# S7CAS-PLEIADES-CARTE-MERE_P06_FPGA1.net
KiCad netlist of a schematic drawn in Altium Designer
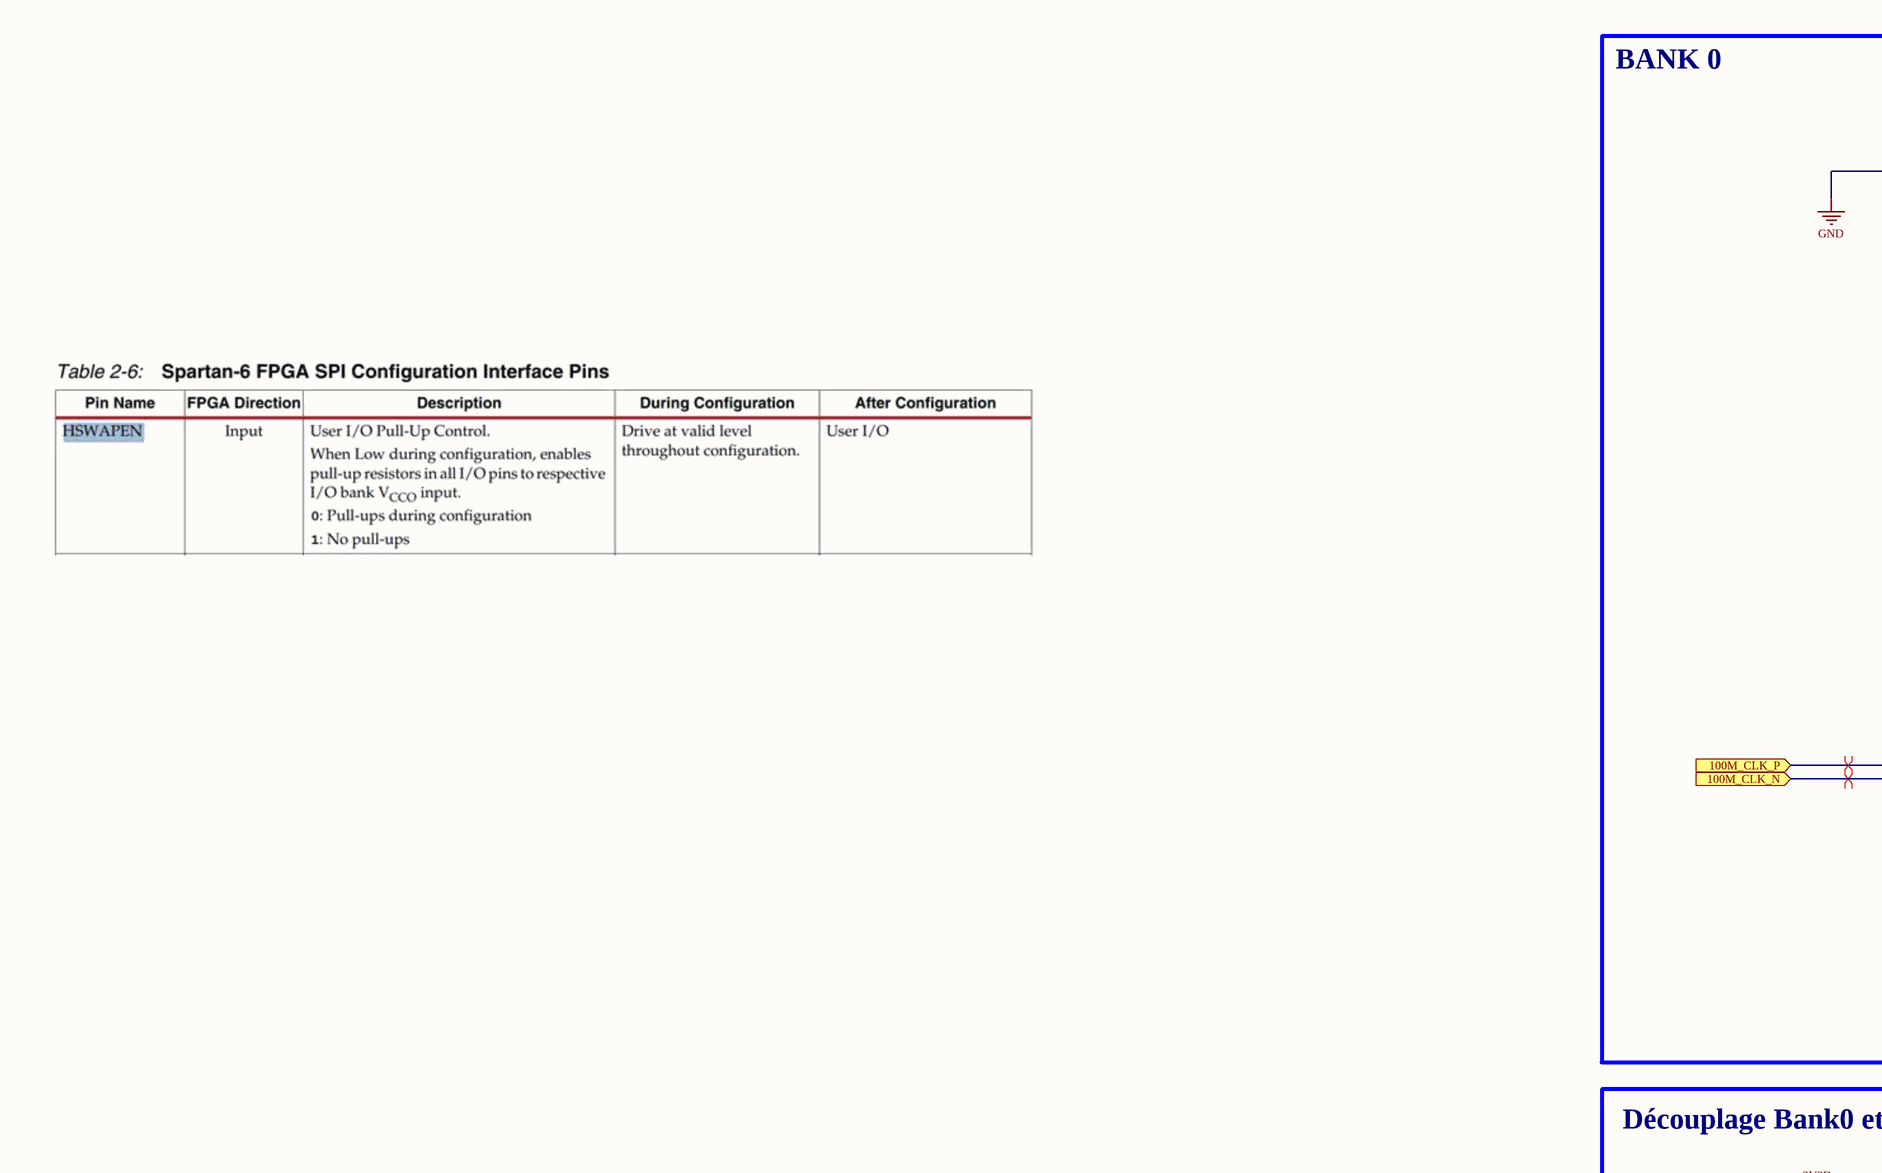
[diagram p0: S7CAS-PLEIADES-CARTE-MERE_P06_FPGA1.SCHDOC, top left]
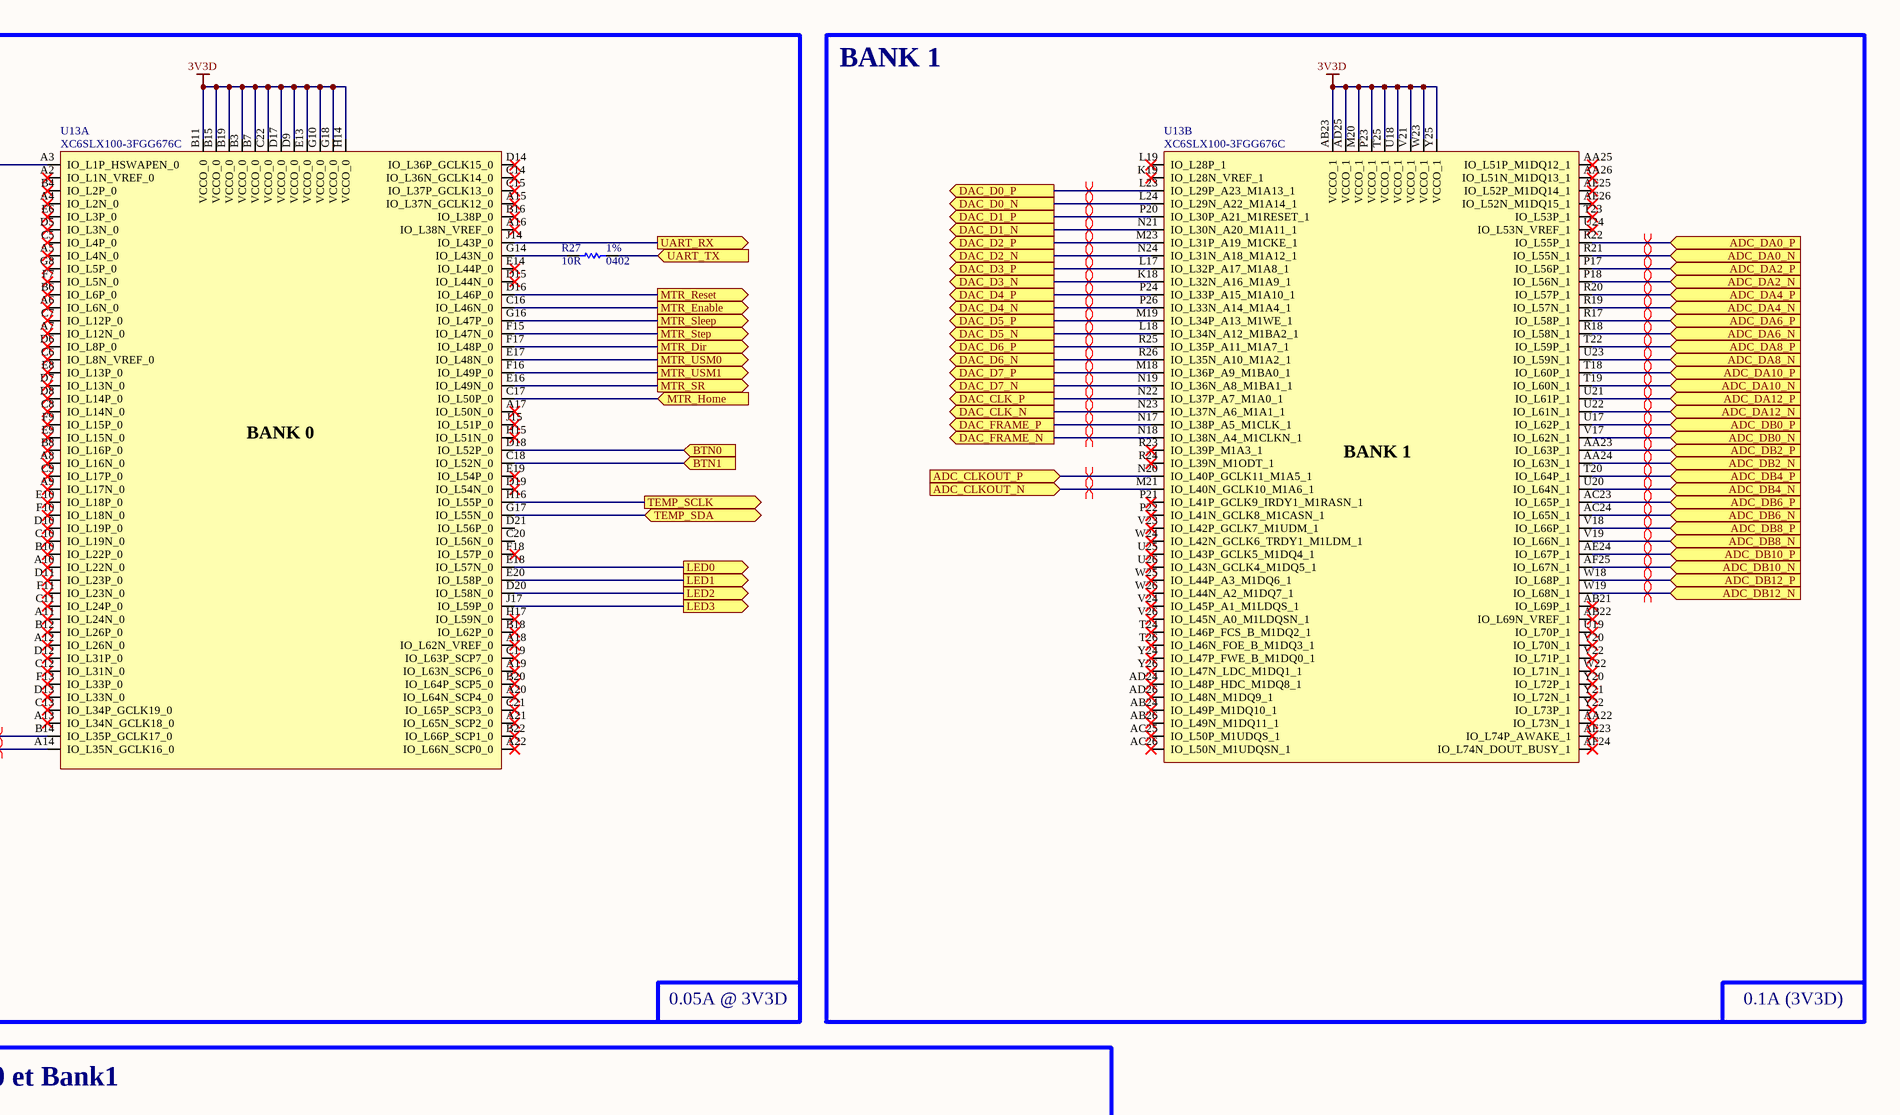
[diagram p1: S7CAS-PLEIADES-CARTE-MERE_P06_FPGA1.SCHDOC, top right]
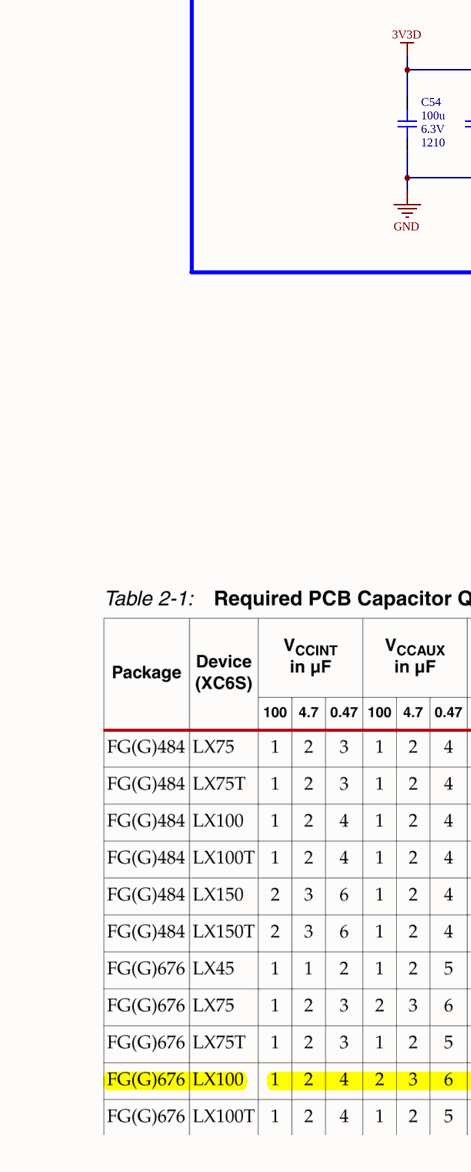
[diagram p2: S7CAS-PLEIADES-CARTE-MERE_P06_FPGA1.SCHDOC, bottom left]
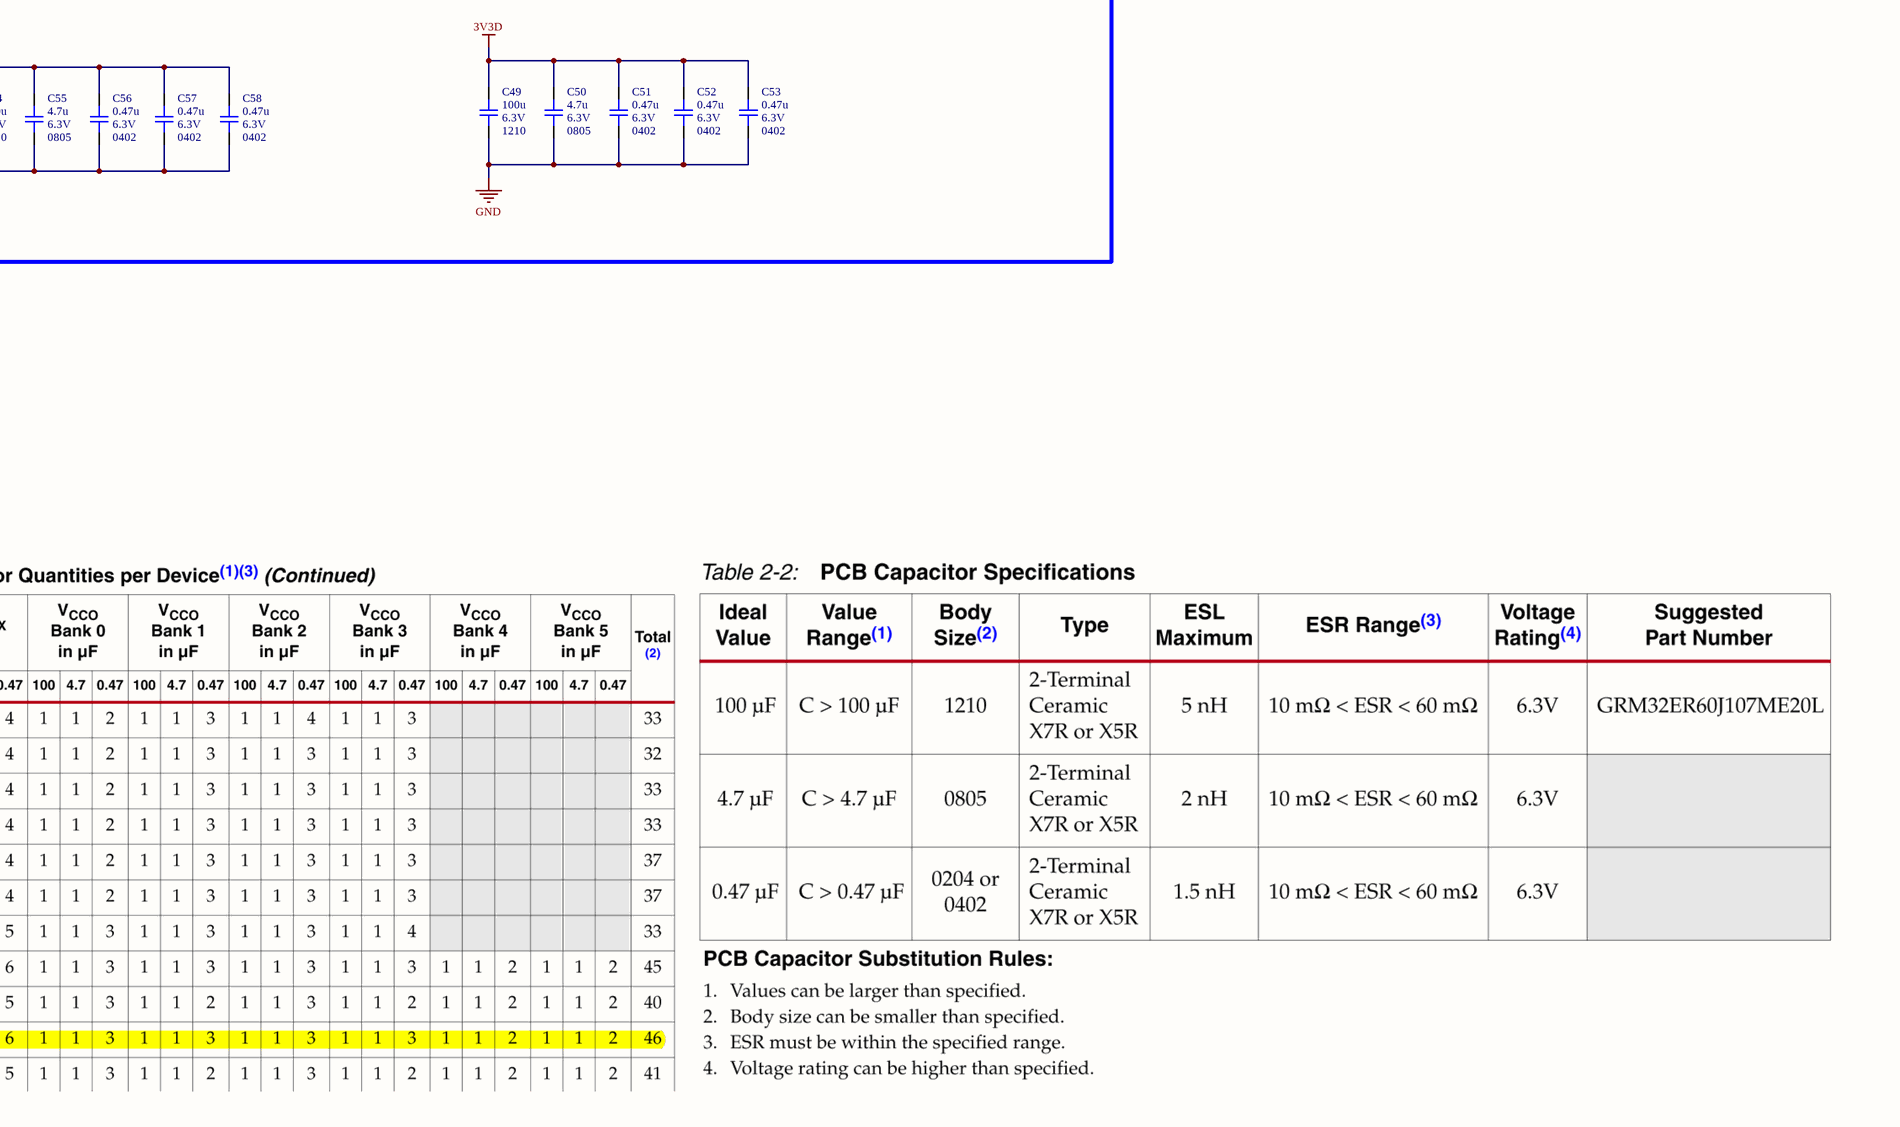
[diagram p3: S7CAS-PLEIADES-CARTE-MERE_P06_FPGA1.SCHDOC, bottom right]

(export (version "E")
  (design (tool "Eeschema 10.0.6"))
  (components
    (comp (ref "C49")
      (value "100u")
      (footprint "CAP_1210")
      (description "CAP - 1210")
      (fields
        (field (name "VOLTAGE") "6.3V")
        (field (name "PACKAGE") "1210")
        (field (name "CREATEDBY") "Jonathan Bouchard")
      )
      (libsource (lib "s7cas_lib2023") (part "CAP - 1210"))
    )
    (comp (ref "C50")
      (value "4.7u")
      (footprint "CAP_0805")
      (description "CAP - 0805")
      (fields
        (field (name "VOLTAGE") "6.3V")
        (field (name "PACKAGE") "0805")
        (field (name "CREATEDBY") "Jonathan Bouchard")
      )
      (libsource (lib "s7cas_lib2023") (part "CAP - 0805"))
    )
    (comp (ref "C51")
      (value "0.47u")
      (footprint "CAP_0402")
      (description "CAP - 0402")
      (fields
        (field (name "VOLTAGE") "6.3V")
        (field (name "PACKAGE") "0402")
        (field (name "CREATEDBY") "Jonathan Bouchard")
      )
      (libsource (lib "s7cas_lib2023") (part "CAP - 0402"))
    )
    (comp (ref "C52")
      (value "0.47u")
      (footprint "CAP_0402")
      (description "CAP - 0402")
      (fields
        (field (name "VOLTAGE") "6.3V")
        (field (name "PACKAGE") "0402")
        (field (name "CREATEDBY") "Jonathan Bouchard")
      )
      (libsource (lib "s7cas_lib2023") (part "CAP - 0402"))
    )
    (comp (ref "C53")
      (value "0.47u")
      (footprint "CAP_0402")
      (description "CAP - 0402")
      (fields
        (field (name "VOLTAGE") "6.3V")
        (field (name "PACKAGE") "0402")
        (field (name "CREATEDBY") "Jonathan Bouchard")
      )
      (libsource (lib "s7cas_lib2023") (part "CAP - 0402"))
    )
    (comp (ref "C54")
      (value "100u")
      (footprint "CAP_1210")
      (description "CAP - 1210")
      (fields
        (field (name "VOLTAGE") "6.3V")
        (field (name "PACKAGE") "1210")
        (field (name "CREATEDBY") "Jonathan Bouchard")
      )
      (libsource (lib "s7cas_lib2023") (part "CAP - 1210"))
    )
    (comp (ref "C55")
      (value "4.7u")
      (footprint "CAP_0805")
      (description "CAP - 0805")
      (fields
        (field (name "VOLTAGE") "6.3V")
        (field (name "PACKAGE") "0805")
        (field (name "CREATEDBY") "Jonathan Bouchard")
      )
      (libsource (lib "s7cas_lib2023") (part "CAP - 0805"))
    )
    (comp (ref "C56")
      (value "0.47u")
      (footprint "CAP_0402")
      (description "CAP - 0402")
      (fields
        (field (name "VOLTAGE") "6.3V")
        (field (name "PACKAGE") "0402")
        (field (name "CREATEDBY") "Jonathan Bouchard")
      )
      (libsource (lib "s7cas_lib2023") (part "CAP - 0402"))
    )
    (comp (ref "C57")
      (value "0.47u")
      (footprint "CAP_0402")
      (description "CAP - 0402")
      (fields
        (field (name "VOLTAGE") "6.3V")
        (field (name "PACKAGE") "0402")
        (field (name "CREATEDBY") "Jonathan Bouchard")
      )
      (libsource (lib "s7cas_lib2023") (part "CAP - 0402"))
    )
    (comp (ref "C58")
      (value "0.47u")
      (footprint "CAP_0402")
      (description "CAP - 0402")
      (fields
        (field (name "VOLTAGE") "6.3V")
        (field (name "PACKAGE") "0402")
        (field (name "CREATEDBY") "Jonathan Bouchard")
      )
      (libsource (lib "s7cas_lib2023") (part "CAP - 0402"))
    )
    (comp (ref "R27")
      (value "10R")
      (footprint "RES_0402")
      (description "RES - 10R 1% 1/16W - 0402")
      (fields
        (field (name "TOLERANCE") "1%")
        (field (name "PACKAGE") "0402")
        (field (name "Comment") "RMCF0402FT10R0")
        (field (name "CREATEDBY/DATE") "Joel Lemay 2018-07-04")
        (field (name "VERIFIEDBY") "Caroline Paulin - 6 sept 2018")
      )
      (libsource (lib "GRAMS_MASTER_LIB") (part "RES_RMCF0402FT10R0"))
    )
    (comp (ref "U13")
      (value "XC6SLX100-3FGG676C")
      (footprint "FPGA_XILINX_FGG676")
      (description "FPGA - XILINX SPARTAN 6 480 I/O - BGA-676")
      (fields
        (field (name "VOLTAGE") "1.14 V ~ 1.26 V")
        (field (name "MFG") "Xilinx")
        (field (name "CREATEDBY") "Jonathan Bouchard")
      )
      (libsource (lib "s7cas_lib2023") (part "FPGA_XC6SLX100-3FGG676C"))
    )
  )
  (nets
    (net (code "1") (name "/100M_CLK_N") (class "Default")
      (node (ref "U13") (pin "A14") (pinfunction "IO_L35N_GCLK16_0_A14") (pintype "passive"))
    )
    (net (code "2") (name "/100M_CLK_P") (class "Default")
      (node (ref "U13") (pin "B14") (pinfunction "IO_L35P_GCLK17_0_B14") (pintype "passive"))
    )
    (net (code "3") (name "/ADC_CLKOUT_N") (class "Default")
      (node (ref "U13") (pin "M21") (pinfunction "IO_L40N_GCLK10_M1A6_1_M21") (pintype "passive"))
    )
    (net (code "4") (name "/ADC_CLKOUT_P") (class "Default")
      (node (ref "U13") (pin "N20") (pinfunction "IO_L40P_GCLK11_M1A5_1_N20") (pintype "passive"))
    )
    (net (code "5") (name "/ADC_DA0_N") (class "Default")
      (node (ref "U13") (pin "R21") (pinfunction "IO_L55N_1_R21") (pintype "passive"))
    )
    (net (code "6") (name "/ADC_DA0_P") (class "Default")
      (node (ref "U13") (pin "R22") (pinfunction "IO_L55P_1_R22") (pintype "passive"))
    )
    (net (code "7") (name "/ADC_DA2_N") (class "Default")
      (node (ref "U13") (pin "P18") (pinfunction "IO_L56N_1_P18") (pintype "passive"))
    )
    (net (code "8") (name "/ADC_DA2_P") (class "Default")
      (node (ref "U13") (pin "P17") (pinfunction "IO_L56P_1_P17") (pintype "passive"))
    )
    (net (code "9") (name "/ADC_DA4_N") (class "Default")
      (node (ref "U13") (pin "R19") (pinfunction "IO_L57N_1_R19") (pintype "passive"))
    )
    (net (code "10") (name "/ADC_DA4_P") (class "Default")
      (node (ref "U13") (pin "R20") (pinfunction "IO_L57P_1_R20") (pintype "passive"))
    )
    (net (code "11") (name "/ADC_DA6_N") (class "Default")
      (node (ref "U13") (pin "R18") (pinfunction "IO_L58N_1_R18") (pintype "passive"))
    )
    (net (code "12") (name "/ADC_DA6_P") (class "Default")
      (node (ref "U13") (pin "R17") (pinfunction "IO_L58P_1_R17") (pintype "passive"))
    )
    (net (code "13") (name "/ADC_DA8_N") (class "Default")
      (node (ref "U13") (pin "U23") (pinfunction "IO_L59N_1_U23") (pintype "passive"))
    )
    (net (code "14") (name "/ADC_DA8_P") (class "Default")
      (node (ref "U13") (pin "T22") (pinfunction "IO_L59P_1_T22") (pintype "passive"))
    )
    (net (code "15") (name "/ADC_DA10_N") (class "Default")
      (node (ref "U13") (pin "T19") (pinfunction "IO_L60N_1_T19") (pintype "passive"))
    )
    (net (code "16") (name "/ADC_DA10_P") (class "Default")
      (node (ref "U13") (pin "T18") (pinfunction "IO_L60P_1_T18") (pintype "passive"))
    )
    (net (code "17") (name "/ADC_DA12_N") (class "Default")
      (node (ref "U13") (pin "U22") (pinfunction "IO_L61N_1_U22") (pintype "passive"))
    )
    (net (code "18") (name "/ADC_DA12_P") (class "Default")
      (node (ref "U13") (pin "U21") (pinfunction "IO_L61P_1_U21") (pintype "passive"))
    )
    (net (code "19") (name "/ADC_DB0_N") (class "Default")
      (node (ref "U13") (pin "V17") (pinfunction "IO_L62N_1_V17") (pintype "passive"))
    )
    (net (code "20") (name "/ADC_DB0_P") (class "Default")
      (node (ref "U13") (pin "U17") (pinfunction "IO_L62P_1_U17") (pintype "passive"))
    )
    (net (code "21") (name "/ADC_DB2_N") (class "Default")
      (node (ref "U13") (pin "AA24") (pinfunction "IO_L63N_1_AA24") (pintype "passive"))
    )
    (net (code "22") (name "/ADC_DB2_P") (class "Default")
      (node (ref "U13") (pin "AA23") (pinfunction "IO_L63P_1_AA23") (pintype "passive"))
    )
    (net (code "23") (name "/ADC_DB4_N") (class "Default")
      (node (ref "U13") (pin "U20") (pinfunction "IO_L64N_1_U20") (pintype "passive"))
    )
    (net (code "24") (name "/ADC_DB4_P") (class "Default")
      (node (ref "U13") (pin "T20") (pinfunction "IO_L64P_1_T20") (pintype "passive"))
    )
    (net (code "25") (name "/ADC_DB6_N") (class "Default")
      (node (ref "U13") (pin "AC24") (pinfunction "IO_L65N_1_AC24") (pintype "passive"))
    )
    (net (code "26") (name "/ADC_DB6_P") (class "Default")
      (node (ref "U13") (pin "AC23") (pinfunction "IO_L65P_1_AC23") (pintype "passive"))
    )
    (net (code "27") (name "/ADC_DB8_N") (class "Default")
      (node (ref "U13") (pin "V19") (pinfunction "IO_L66N_1_V19") (pintype "passive"))
    )
    (net (code "28") (name "/ADC_DB8_P") (class "Default")
      (node (ref "U13") (pin "V18") (pinfunction "IO_L66P_1_V18") (pintype "passive"))
    )
    (net (code "29") (name "/ADC_DB10_N") (class "Default")
      (node (ref "U13") (pin "AF25") (pinfunction "IO_L67N_1_AF25") (pintype "passive"))
    )
    (net (code "30") (name "/ADC_DB10_P") (class "Default")
      (node (ref "U13") (pin "AE24") (pinfunction "IO_L67P_1_AE24") (pintype "passive"))
    )
    (net (code "31") (name "/ADC_DB12_N") (class "Default")
      (node (ref "U13") (pin "W19") (pinfunction "IO_L68N_1_W19") (pintype "passive"))
    )
    (net (code "32") (name "/ADC_DB12_P") (class "Default")
      (node (ref "U13") (pin "W18") (pinfunction "IO_L68P_1_W18") (pintype "passive"))
    )
    (net (code "33") (name "/BTN0") (class "Default")
      (node (ref "U13") (pin "D18") (pinfunction "IO_L52P_0_D18") (pintype "passive"))
    )
    (net (code "34") (name "/BTN1") (class "Default")
      (node (ref "U13") (pin "C18") (pinfunction "IO_L52N_0_C18") (pintype "passive"))
    )
    (net (code "35") (name "/DAC_CLK_N") (class "Default")
      (node (ref "U13") (pin "N23") (pinfunction "IO_L37N_A6_M1A1_1_N23") (pintype "passive"))
    )
    (net (code "36") (name "/DAC_CLK_P") (class "Default")
      (node (ref "U13") (pin "N22") (pinfunction "IO_L37P_A7_M1A0_1_N22") (pintype "passive"))
    )
    (net (code "37") (name "/DAC_D0_N") (class "Default")
      (node (ref "U13") (pin "L24") (pinfunction "IO_L29N_A22_M1A14_1_L24") (pintype "passive"))
    )
    (net (code "38") (name "/DAC_D0_P") (class "Default")
      (node (ref "U13") (pin "L23") (pinfunction "IO_L29P_A23_M1A13_1_L23") (pintype "passive"))
    )
    (net (code "39") (name "/DAC_D1_N") (class "Default")
      (node (ref "U13") (pin "N21") (pinfunction "IO_L30N_A20_M1A11_1_N21") (pintype "passive"))
    )
    (net (code "40") (name "/DAC_D1_P") (class "Default")
      (node (ref "U13") (pin "P20") (pinfunction "IO_L30P_A21_M1RESET_1_P20") (pintype "passive"))
    )
    (net (code "41") (name "/DAC_D2_N") (class "Default")
      (node (ref "U13") (pin "N24") (pinfunction "IO_L31N_A18_M1A12_1_N24") (pintype "passive"))
    )
    (net (code "42") (name "/DAC_D2_P") (class "Default")
      (node (ref "U13") (pin "M23") (pinfunction "IO_L31P_A19_M1CKE_1_M23") (pintype "passive"))
    )
    (net (code "43") (name "/DAC_D3_N") (class "Default")
      (node (ref "U13") (pin "K18") (pinfunction "IO_L32N_A16_M1A9_1_K18") (pintype "passive"))
    )
    (net (code "44") (name "/DAC_D3_P") (class "Default")
      (node (ref "U13") (pin "L17") (pinfunction "IO_L32P_A17_M1A8_1_L17") (pintype "passive"))
    )
    (net (code "45") (name "/DAC_D4_N") (class "Default")
      (node (ref "U13") (pin "P26") (pinfunction "IO_L33N_A14_M1A4_1_P26") (pintype "passive"))
    )
    (net (code "46") (name "/DAC_D4_P") (class "Default")
      (node (ref "U13") (pin "P24") (pinfunction "IO_L33P_A15_M1A10_1_P24") (pintype "passive"))
    )
    (net (code "47") (name "/DAC_D5_N") (class "Default")
      (node (ref "U13") (pin "L18") (pinfunction "IO_L34N_A12_M1BA2_1_L18") (pintype "passive"))
    )
    (net (code "48") (name "/DAC_D5_P") (class "Default")
      (node (ref "U13") (pin "M19") (pinfunction "IO_L34P_A13_M1WE_1_M19") (pintype "passive"))
    )
    (net (code "49") (name "/DAC_D6_N") (class "Default")
      (node (ref "U13") (pin "R26") (pinfunction "IO_L35N_A10_M1A2_1_R26") (pintype "passive"))
    )
    (net (code "50") (name "/DAC_D6_P") (class "Default")
      (node (ref "U13") (pin "R25") (pinfunction "IO_L35P_A11_M1A7_1_R25") (pintype "passive"))
    )
    (net (code "51") (name "/DAC_D7_N") (class "Default")
      (node (ref "U13") (pin "N19") (pinfunction "IO_L36N_A8_M1BA1_1_N19") (pintype "passive"))
    )
    (net (code "52") (name "/DAC_D7_P") (class "Default")
      (node (ref "U13") (pin "M18") (pinfunction "IO_L36P_A9_M1BA0_1_M18") (pintype "passive"))
    )
    (net (code "53") (name "/DAC_FRAME_N") (class "Default")
      (node (ref "U13") (pin "N18") (pinfunction "IO_L38N_A4_M1CLKN_1_N18") (pintype "passive"))
    )
    (net (code "54") (name "/DAC_FRAME_P") (class "Default")
      (node (ref "U13") (pin "N17") (pinfunction "IO_L38P_A5_M1CLK_1_N17") (pintype "passive"))
    )
    (net (code "55") (name "/LED0") (class "Default")
      (node (ref "U13") (pin "E18") (pinfunction "IO_L57N_0_E18") (pintype "passive"))
    )
    (net (code "56") (name "/LED1") (class "Default")
      (node (ref "U13") (pin "E20") (pinfunction "IO_L58P_0_E20") (pintype "passive"))
    )
    (net (code "57") (name "/LED2") (class "Default")
      (node (ref "U13") (pin "D20") (pinfunction "IO_L58N_0_D20") (pintype "passive"))
    )
    (net (code "58") (name "/LED3") (class "Default")
      (node (ref "U13") (pin "J17") (pinfunction "IO_L59P_0_J17") (pintype "passive"))
    )
    (net (code "59") (name "/MTR_Dir") (class "Default")
      (node (ref "U13") (pin "F17") (pinfunction "IO_L48P_0_F17") (pintype "passive"))
    )
    (net (code "60") (name "/MTR_Enable") (class "Default")
      (node (ref "U13") (pin "C16") (pinfunction "IO_L46N_0_C16") (pintype "passive"))
    )
    (net (code "61") (name "/MTR_Home") (class "Default")
      (node (ref "U13") (pin "C17") (pinfunction "IO_L50P_0_C17") (pintype "passive"))
    )
    (net (code "62") (name "/MTR_Reset") (class "Default")
      (node (ref "U13") (pin "D16") (pinfunction "IO_L46P_0_D16") (pintype "passive"))
    )
    (net (code "63") (name "/MTR_SR") (class "Default")
      (node (ref "U13") (pin "E16") (pinfunction "IO_L49N_0_E16") (pintype "passive"))
    )
    (net (code "64") (name "/MTR_Sleep") (class "Default")
      (node (ref "U13") (pin "G16") (pinfunction "IO_L47P_0_G16") (pintype "passive"))
    )
    (net (code "65") (name "/MTR_Step") (class "Default")
      (node (ref "U13") (pin "F15") (pinfunction "IO_L47N_0_F15") (pintype "passive"))
    )
    (net (code "66") (name "/MTR_USM0") (class "Default")
      (node (ref "U13") (pin "E17") (pinfunction "IO_L48N_0_E17") (pintype "passive"))
    )
    (net (code "67") (name "/MTR_USM1") (class "Default")
      (node (ref "U13") (pin "F16") (pinfunction "IO_L49P_0_F16") (pintype "passive"))
    )
    (net (code "68") (name "/TEMP_SCLK") (class "Default")
      (node (ref "U13") (pin "H16") (pinfunction "IO_L55P_0_H16") (pintype "passive"))
    )
    (net (code "69") (name "/TEMP_SDA") (class "Default")
      (node (ref "U13") (pin "G17") (pinfunction "IO_L55N_0_G17") (pintype "passive"))
    )
    (net (code "70") (name "/UART_RX") (class "Default")
      (node (ref "U13") (pin "J14") (pinfunction "IO_L43P_0_J14") (pintype "passive"))
    )
    (net (code "71") (name "/UART_TX") (class "Default")
      (node (ref "R27") (pin "1") (pinfunction "1_1") (pintype "passive"))
    )
    (net (code "72") (name "3V3D") (class "Default")
      (node (ref "C49") (pin "2") (pinfunction "2_2") (pintype "passive"))
      (node (ref "C50") (pin "2") (pinfunction "2_2") (pintype "passive"))
      (node (ref "C51") (pin "2") (pinfunction "2_2") (pintype "passive"))
      (node (ref "C52") (pin "2") (pinfunction "2_2") (pintype "passive"))
      (node (ref "C53") (pin "2") (pinfunction "2_2") (pintype "passive"))
      (node (ref "C54") (pin "2") (pinfunction "2_2") (pintype "passive"))
      (node (ref "C55") (pin "2") (pinfunction "2_2") (pintype "passive"))
      (node (ref "C56") (pin "2") (pinfunction "2_2") (pintype "passive"))
      (node (ref "C57") (pin "2") (pinfunction "2_2") (pintype "passive"))
      (node (ref "C58") (pin "2") (pinfunction "2_2") (pintype "passive"))
      (node (ref "U13") (pin "AB23") (pinfunction "VCCO_1_AB23") (pintype "passive"))
      (node (ref "U13") (pin "AD25") (pinfunction "VCCO_1_AD25") (pintype "passive"))
      (node (ref "U13") (pin "B11") (pinfunction "VCCO_0_B11") (pintype "passive"))
      (node (ref "U13") (pin "B15") (pinfunction "VCCO_0_B15") (pintype "passive"))
      (node (ref "U13") (pin "B19") (pinfunction "VCCO_0_B19") (pintype "passive"))
      (node (ref "U13") (pin "B3") (pinfunction "VCCO_0_B3") (pintype "passive"))
      (node (ref "U13") (pin "B7") (pinfunction "VCCO_0_B7") (pintype "passive"))
      (node (ref "U13") (pin "C22") (pinfunction "VCCO_0_C22") (pintype "passive"))
      (node (ref "U13") (pin "D17") (pinfunction "VCCO_0_D17") (pintype "passive"))
      (node (ref "U13") (pin "D9") (pinfunction "VCCO_0_D9") (pintype "passive"))
      (node (ref "U13") (pin "E13") (pinfunction "VCCO_0_E13") (pintype "passive"))
      (node (ref "U13") (pin "G10") (pinfunction "VCCO_0_G10") (pintype "passive"))
      (node (ref "U13") (pin "G18") (pinfunction "VCCO_0_G18") (pintype "passive"))
      (node (ref "U13") (pin "H14") (pinfunction "VCCO_0_H14") (pintype "passive"))
      (node (ref "U13") (pin "M20") (pinfunction "VCCO_1_M20") (pintype "passive"))
      (node (ref "U13") (pin "P23") (pinfunction "VCCO_1_P23") (pintype "passive"))
      (node (ref "U13") (pin "T25") (pinfunction "VCCO_1_T25") (pintype "passive"))
      (node (ref "U13") (pin "U18") (pinfunction "VCCO_1_U18") (pintype "passive"))
      (node (ref "U13") (pin "V21") (pinfunction "VCCO_1_V21") (pintype "passive"))
      (node (ref "U13") (pin "W23") (pinfunction "VCCO_1_W23") (pintype "passive"))
      (node (ref "U13") (pin "Y25") (pinfunction "VCCO_1_Y25") (pintype "passive"))
    )
    (net (code "73") (name "GND") (class "Default")
      (node (ref "C49") (pin "1") (pinfunction "1_1") (pintype "passive"))
      (node (ref "C50") (pin "1") (pinfunction "1_1") (pintype "passive"))
      (node (ref "C51") (pin "1") (pinfunction "1_1") (pintype "passive"))
      (node (ref "C52") (pin "1") (pinfunction "1_1") (pintype "passive"))
      (node (ref "C53") (pin "1") (pinfunction "1_1") (pintype "passive"))
      (node (ref "C54") (pin "1") (pinfunction "1_1") (pintype "passive"))
      (node (ref "C55") (pin "1") (pinfunction "1_1") (pintype "passive"))
      (node (ref "C56") (pin "1") (pinfunction "1_1") (pintype "passive"))
      (node (ref "C57") (pin "1") (pinfunction "1_1") (pintype "passive"))
      (node (ref "C58") (pin "1") (pinfunction "1_1") (pintype "passive"))
      (node (ref "U13") (pin "A3") (pinfunction "IO_L1P_HSWAPEN_0_A3") (pintype "passive"))
    )
    (net (code "74") (name "Net-(U13A-IO_L43N_0)") (class "Default")
      (node (ref "R27") (pin "2") (pinfunction "2_2") (pintype "passive"))
      (node (ref "U13") (pin "G14") (pinfunction "IO_L43N_0_G14") (pintype "passive"))
    )
    (net (code "75") (name "unconnected-(U13A-IO_L1N_VREF_0-PadA2)") (class "Default")
      (node (ref "U13") (pin "A2") (pinfunction "IO_L1N_VREF_0_A2") (pintype "passive+no_connect"))
    )
    (net (code "76") (name "unconnected-(U13A-IO_L2N_0-PadA4)") (class "Default")
      (node (ref "U13") (pin "A4") (pinfunction "IO_L2N_0_A4") (pintype "passive+no_connect"))
    )
    (net (code "77") (name "unconnected-(U13A-IO_L2P_0-PadB4)") (class "Default")
      (node (ref "U13") (pin "B4") (pinfunction "IO_L2P_0_B4") (pintype "passive+no_connect"))
    )
    (net (code "78") (name "unconnected-(U13A-IO_L3N_0-PadD5)") (class "Default")
      (node (ref "U13") (pin "D5") (pinfunction "IO_L3N_0_D5") (pintype "passive+no_connect"))
    )
    (net (code "79") (name "unconnected-(U13A-IO_L3P_0-PadE6)") (class "Default")
      (node (ref "U13") (pin "E6") (pinfunction "IO_L3P_0_E6") (pintype "passive+no_connect"))
    )
    (net (code "80") (name "unconnected-(U13A-IO_L4N_0-PadA5)") (class "Default")
      (node (ref "U13") (pin "A5") (pinfunction "IO_L4N_0_A5") (pintype "passive+no_connect"))
    )
    (net (code "81") (name "unconnected-(U13A-IO_L4P_0-PadC5)") (class "Default")
      (node (ref "U13") (pin "C5") (pinfunction "IO_L4P_0_C5") (pintype "passive+no_connect"))
    )
    (net (code "82") (name "unconnected-(U13A-IO_L5N_0-PadF7)") (class "Default")
      (node (ref "U13") (pin "F7") (pinfunction "IO_L5N_0_F7") (pintype "passive+no_connect"))
    )
    (net (code "83") (name "unconnected-(U13A-IO_L5P_0-PadG8)") (class "Default")
      (node (ref "U13") (pin "G8") (pinfunction "IO_L5P_0_G8") (pintype "passive+no_connect"))
    )
    (net (code "84") (name "unconnected-(U13A-IO_L6N_0-PadA6)") (class "Default")
      (node (ref "U13") (pin "A6") (pinfunction "IO_L6N_0_A6") (pintype "passive+no_connect"))
    )
    (net (code "85") (name "unconnected-(U13A-IO_L6P_0-PadB6)") (class "Default")
      (node (ref "U13") (pin "B6") (pinfunction "IO_L6P_0_B6") (pintype "passive+no_connect"))
    )
    (net (code "86") (name "unconnected-(U13A-IO_L8N_VREF_0-PadC6)") (class "Default")
      (node (ref "U13") (pin "C6") (pinfunction "IO_L8N_VREF_0_C6") (pintype "passive+no_connect"))
    )
    (net (code "87") (name "unconnected-(U13A-IO_L8P_0-PadD6)") (class "Default")
      (node (ref "U13") (pin "D6") (pinfunction "IO_L8P_0_D6") (pintype "passive+no_connect"))
    )
    (net (code "88") (name "unconnected-(U13A-IO_L12N_0-PadA7)") (class "Default")
      (node (ref "U13") (pin "A7") (pinfunction "IO_L12N_0_A7") (pintype "passive+no_connect"))
    )
    (net (code "89") (name "unconnected-(U13A-IO_L12P_0-PadC7)") (class "Default")
      (node (ref "U13") (pin "C7") (pinfunction "IO_L12P_0_C7") (pintype "passive+no_connect"))
    )
    (net (code "90") (name "unconnected-(U13A-IO_L13N_0-PadD7)") (class "Default")
      (node (ref "U13") (pin "D7") (pinfunction "IO_L13N_0_D7") (pintype "passive+no_connect"))
    )
    (net (code "91") (name "unconnected-(U13A-IO_L13P_0-PadE8)") (class "Default")
      (node (ref "U13") (pin "E8") (pinfunction "IO_L13P_0_E8") (pintype "passive+no_connect"))
    )
    (net (code "92") (name "unconnected-(U13A-IO_L14N_0-PadC8)") (class "Default")
      (node (ref "U13") (pin "C8") (pinfunction "IO_L14N_0_C8") (pintype "passive+no_connect"))
    )
    (net (code "93") (name "unconnected-(U13A-IO_L14P_0-PadD8)") (class "Default")
      (node (ref "U13") (pin "D8") (pinfunction "IO_L14P_0_D8") (pintype "passive+no_connect"))
    )
    (net (code "94") (name "unconnected-(U13A-IO_L15N_0-PadE9)") (class "Default")
      (node (ref "U13") (pin "E9") (pinfunction "IO_L15N_0_E9") (pintype "passive+no_connect"))
    )
    (net (code "95") (name "unconnected-(U13A-IO_L15P_0-PadF9)") (class "Default")
      (node (ref "U13") (pin "F9") (pinfunction "IO_L15P_0_F9") (pintype "passive+no_connect"))
    )
    (net (code "96") (name "unconnected-(U13A-IO_L16N_0-PadA8)") (class "Default")
      (node (ref "U13") (pin "A8") (pinfunction "IO_L16N_0_A8") (pintype "passive+no_connect"))
    )
    (net (code "97") (name "unconnected-(U13A-IO_L16P_0-PadB8)") (class "Default")
      (node (ref "U13") (pin "B8") (pinfunction "IO_L16P_0_B8") (pintype "passive+no_connect"))
    )
    (net (code "98") (name "unconnected-(U13A-IO_L17N_0-PadA9)") (class "Default")
      (node (ref "U13") (pin "A9") (pinfunction "IO_L17N_0_A9") (pintype "passive+no_connect"))
    )
    (net (code "99") (name "unconnected-(U13A-IO_L17P_0-PadC9)") (class "Default")
      (node (ref "U13") (pin "C9") (pinfunction "IO_L17P_0_C9") (pintype "passive+no_connect"))
    )
    (net (code "100") (name "unconnected-(U13A-IO_L18N_0-PadF10)") (class "Default")
      (node (ref "U13") (pin "F10") (pinfunction "IO_L18N_0_F10") (pintype "passive+no_connect"))
    )
    (net (code "101") (name "unconnected-(U13A-IO_L18P_0-PadE10)") (class "Default")
      (node (ref "U13") (pin "E10") (pinfunction "IO_L18P_0_E10") (pintype "passive+no_connect"))
    )
    (net (code "102") (name "unconnected-(U13A-IO_L19N_0-PadC10)") (class "Default")
      (node (ref "U13") (pin "C10") (pinfunction "IO_L19N_0_C10") (pintype "passive+no_connect"))
    )
    (net (code "103") (name "unconnected-(U13A-IO_L19P_0-PadD10)") (class "Default")
      (node (ref "U13") (pin "D10") (pinfunction "IO_L19P_0_D10") (pintype "passive+no_connect"))
    )
    (net (code "104") (name "unconnected-(U13A-IO_L22N_0-PadA10)") (class "Default")
      (node (ref "U13") (pin "A10") (pinfunction "IO_L22N_0_A10") (pintype "passive+no_connect"))
    )
    (net (code "105") (name "unconnected-(U13A-IO_L22P_0-PadB10)") (class "Default")
      (node (ref "U13") (pin "B10") (pinfunction "IO_L22P_0_B10") (pintype "passive+no_connect"))
    )
    (net (code "106") (name "unconnected-(U13A-IO_L23N_0-PadF11)") (class "Default")
      (node (ref "U13") (pin "F11") (pinfunction "IO_L23N_0_F11") (pintype "passive+no_connect"))
    )
    (net (code "107") (name "unconnected-(U13A-IO_L23P_0-PadD11)") (class "Default")
      (node (ref "U13") (pin "D11") (pinfunction "IO_L23P_0_D11") (pintype "passive+no_connect"))
    )
    (net (code "108") (name "unconnected-(U13A-IO_L24N_0-PadA11)") (class "Default")
      (node (ref "U13") (pin "A11") (pinfunction "IO_L24N_0_A11") (pintype "passive+no_connect"))
    )
    (net (code "109") (name "unconnected-(U13A-IO_L24P_0-PadC11)") (class "Default")
      (node (ref "U13") (pin "C11") (pinfunction "IO_L24P_0_C11") (pintype "passive+no_connect"))
    )
    (net (code "110") (name "unconnected-(U13A-IO_L26N_0-PadA12)") (class "Default")
      (node (ref "U13") (pin "A12") (pinfunction "IO_L26N_0_A12") (pintype "passive+no_connect"))
    )
    (net (code "111") (name "unconnected-(U13A-IO_L26P_0-PadB12)") (class "Default")
      (node (ref "U13") (pin "B12") (pinfunction "IO_L26P_0_B12") (pintype "passive+no_connect"))
    )
    (net (code "112") (name "unconnected-(U13A-IO_L31N_0-PadC12)") (class "Default")
      (node (ref "U13") (pin "C12") (pinfunction "IO_L31N_0_C12") (pintype "passive+no_connect"))
    )
    (net (code "113") (name "unconnected-(U13A-IO_L31P_0-PadD12)") (class "Default")
      (node (ref "U13") (pin "D12") (pinfunction "IO_L31P_0_D12") (pintype "passive+no_connect"))
    )
    (net (code "114") (name "unconnected-(U13A-IO_L33N_0-PadD13)") (class "Default")
      (node (ref "U13") (pin "D13") (pinfunction "IO_L33N_0_D13") (pintype "passive+no_connect"))
    )
    (net (code "115") (name "unconnected-(U13A-IO_L33P_0-PadF13)") (class "Default")
      (node (ref "U13") (pin "F13") (pinfunction "IO_L33P_0_F13") (pintype "passive+no_connect"))
    )
    (net (code "116") (name "unconnected-(U13A-IO_L34N_GCLK18_0-PadA13)") (class "Default")
      (node (ref "U13") (pin "A13") (pinfunction "IO_L34N_GCLK18_0_A13") (pintype "passive+no_connect"))
    )
    (net (code "117") (name "unconnected-(U13A-IO_L34P_GCLK19_0-PadC13)") (class "Default")
      (node (ref "U13") (pin "C13") (pinfunction "IO_L34P_GCLK19_0_C13") (pintype "passive+no_connect"))
    )
    (net (code "118") (name "unconnected-(U13A-IO_L36N_GCLK14_0-PadC14)") (class "Default")
      (node (ref "U13") (pin "C14") (pinfunction "IO_L36N_GCLK14_0_C14") (pintype "passive+no_connect"))
    )
    (net (code "119") (name "unconnected-(U13A-IO_L36P_GCLK15_0-PadD14)") (class "Default")
      (node (ref "U13") (pin "D14") (pinfunction "IO_L36P_GCLK15_0_D14") (pintype "passive+no_connect"))
    )
    (net (code "120") (name "unconnected-(U13A-IO_L37N_GCLK12_0-PadA15)") (class "Default")
      (node (ref "U13") (pin "A15") (pinfunction "IO_L37N_GCLK12_0_A15") (pintype "passive+no_connect"))
    )
    (net (code "121") (name "unconnected-(U13A-IO_L37P_GCLK13_0-PadC15)") (class "Default")
      (node (ref "U13") (pin "C15") (pinfunction "IO_L37P_GCLK13_0_C15") (pintype "passive+no_connect"))
    )
    (net (code "122") (name "unconnected-(U13A-IO_L38N_VREF_0-PadA16)") (class "Default")
      (node (ref "U13") (pin "A16") (pinfunction "IO_L38N_VREF_0_A16") (pintype "passive+no_connect"))
    )
    (net (code "123") (name "unconnected-(U13A-IO_L38P_0-PadB16)") (class "Default")
      (node (ref "U13") (pin "B16") (pinfunction "IO_L38P_0_B16") (pintype "passive+no_connect"))
    )
    (net (code "124") (name "unconnected-(U13A-IO_L44N_0-PadD15)") (class "Default")
      (node (ref "U13") (pin "D15") (pinfunction "IO_L44N_0_D15") (pintype "passive+no_connect"))
    )
    (net (code "125") (name "unconnected-(U13A-IO_L44P_0-PadE14)") (class "Default")
      (node (ref "U13") (pin "E14") (pinfunction "IO_L44P_0_E14") (pintype "passive+no_connect"))
    )
    (net (code "126") (name "unconnected-(U13A-IO_L50N_0-PadA17)") (class "Default")
      (node (ref "U13") (pin "A17") (pinfunction "IO_L50N_0_A17") (pintype "passive+no_connect"))
    )
    (net (code "127") (name "unconnected-(U13A-IO_L51N_0-PadH15)") (class "Default")
      (node (ref "U13") (pin "H15") (pinfunction "IO_L51N_0_H15") (pintype "passive+no_connect"))
    )
    (net (code "128") (name "unconnected-(U13A-IO_L51P_0-PadJ15)") (class "Default")
      (node (ref "U13") (pin "J15") (pinfunction "IO_L51P_0_J15") (pintype "passive+no_connect"))
    )
    (net (code "129") (name "unconnected-(U13A-IO_L54N_0-PadD19)") (class "Default")
      (node (ref "U13") (pin "D19") (pinfunction "IO_L54N_0_D19") (pintype "passive+no_connect"))
    )
    (net (code "130") (name "unconnected-(U13A-IO_L54P_0-PadE19)") (class "Default")
      (node (ref "U13") (pin "E19") (pinfunction "IO_L54P_0_E19") (pintype "passive+no_connect"))
    )
    (net (code "131") (name "unconnected-(U13A-IO_L56N_0-PadC20)") (class "Default")
      (node (ref "U13") (pin "C20") (pinfunction "IO_L56N_0_C20") (pintype "passive"))
    )
    (net (code "132") (name "unconnected-(U13A-IO_L56P_0-PadD21)") (class "Default")
      (node (ref "U13") (pin "D21") (pinfunction "IO_L56P_0_D21") (pintype "passive"))
    )
    (net (code "133") (name "unconnected-(U13A-IO_L57P_0-PadF18)") (class "Default")
      (node (ref "U13") (pin "F18") (pinfunction "IO_L57P_0_F18") (pintype "passive+no_connect"))
    )
    (net (code "134") (name "unconnected-(U13A-IO_L59N_0-PadH17)") (class "Default")
      (node (ref "U13") (pin "H17") (pinfunction "IO_L59N_0_H17") (pintype "passive+no_connect"))
    )
    (net (code "135") (name "unconnected-(U13A-IO_L62N_VREF_0-PadA18)") (class "Default")
      (node (ref "U13") (pin "A18") (pinfunction "IO_L62N_VREF_0_A18") (pintype "passive+no_connect"))
    )
    (net (code "136") (name "unconnected-(U13A-IO_L62P_0-PadB18)") (class "Default")
      (node (ref "U13") (pin "B18") (pinfunction "IO_L62P_0_B18") (pintype "passive+no_connect"))
    )
    (net (code "137") (name "unconnected-(U13A-IO_L63N_SCP6_0-PadA19)") (class "Default")
      (node (ref "U13") (pin "A19") (pinfunction "IO_L63N_SCP6_0_A19") (pintype "passive+no_connect"))
    )
    (net (code "138") (name "unconnected-(U13A-IO_L63P_SCP7_0-PadC19)") (class "Default")
      (node (ref "U13") (pin "C19") (pinfunction "IO_L63P_SCP7_0_C19") (pintype "passive+no_connect"))
    )
    (net (code "139") (name "unconnected-(U13A-IO_L64N_SCP4_0-PadA20)") (class "Default")
      (node (ref "U13") (pin "A20") (pinfunction "IO_L64N_SCP4_0_A20") (pintype "passive+no_connect"))
    )
    (net (code "140") (name "unconnected-(U13A-IO_L64P_SCP5_0-PadB20)") (class "Default")
      (node (ref "U13") (pin "B20") (pinfunction "IO_L64P_SCP5_0_B20") (pintype "passive+no_connect"))
    )
    (net (code "141") (name "unconnected-(U13A-IO_L65N_SCP2_0-PadA21)") (class "Default")
      (node (ref "U13") (pin "A21") (pinfunction "IO_L65N_SCP2_0_A21") (pintype "passive+no_connect"))
    )
    (net (code "142") (name "unconnected-(U13A-IO_L65P_SCP3_0-PadC21)") (class "Default")
      (node (ref "U13") (pin "C21") (pinfunction "IO_L65P_SCP3_0_C21") (pintype "passive+no_connect"))
    )
    (net (code "143") (name "unconnected-(U13A-IO_L66N_SCP0_0-PadA22)") (class "Default")
      (node (ref "U13") (pin "A22") (pinfunction "IO_L66N_SCP0_0_A22") (pintype "passive+no_connect"))
    )
    (net (code "144") (name "unconnected-(U13A-IO_L66P_SCP1_0-PadB22)") (class "Default")
      (node (ref "U13") (pin "B22") (pinfunction "IO_L66P_SCP1_0_B22") (pintype "passive+no_connect"))
    )
    (net (code "145") (name "unconnected-(U13B-IO_L28N_VREF_1-PadK19)") (class "Default")
      (node (ref "U13") (pin "K19") (pinfunction "IO_L28N_VREF_1_K19") (pintype "passive+no_connect"))
    )
    (net (code "146") (name "unconnected-(U13B-IO_L28P_1-PadL19)") (class "Default")
      (node (ref "U13") (pin "L19") (pinfunction "IO_L28P_1_L19") (pintype "passive+no_connect"))
    )
    (net (code "147") (name "unconnected-(U13B-IO_L39N_M1ODT_1-PadR24)") (class "Default")
      (node (ref "U13") (pin "R24") (pinfunction "IO_L39N_M1ODT_1_R24") (pintype "passive+no_connect"))
    )
    (net (code "148") (name "unconnected-(U13B-IO_L39P_M1A3_1-PadR23)") (class "Default")
      (node (ref "U13") (pin "R23") (pinfunction "IO_L39P_M1A3_1_R23") (pintype "passive+no_connect"))
    )
    (net (code "149") (name "unconnected-(U13B-IO_L41N_GCLK8_M1CASN_1-PadP22)") (class "Default")
      (node (ref "U13") (pin "P22") (pinfunction "IO_L41N_GCLK8_M1CASN_1_P22") (pintype "passive+no_connect"))
    )
    (net (code "150") (name "unconnected-(U13B-IO_L41P_GCLK9_IRDY1_M1RASN_1-PadP21)") (class "Default")
      (node (ref "U13") (pin "P21") (pinfunction "IO_L41P_GCLK9_IRDY1_M1RASN_1_P21") (pintype "passive+no_connect"))
    )
    (net (code "151") (name "unconnected-(U13B-IO_L42N_GCLK6_TRDY1_M1LDM_1-PadW24)") (class "Default")
      (node (ref "U13") (pin "W24") (pinfunction "IO_L42N_GCLK6_TRDY1_M1LDM_1_W24") (pintype "passive+no_connect"))
    )
    (net (code "152") (name "unconnected-(U13B-IO_L42P_GCLK7_M1UDM_1-PadV23)") (class "Default")
      (node (ref "U13") (pin "V23") (pinfunction "IO_L42P_GCLK7_M1UDM_1_V23") (pintype "passive+no_connect"))
    )
    (net (code "153") (name "unconnected-(U13B-IO_L43N_GCLK4_M1DQ5_1-PadU26)") (class "Default")
      (node (ref "U13") (pin "U26") (pinfunction "IO_L43N_GCLK4_M1DQ5_1_U26") (pintype "passive+no_connect"))
    )
    (net (code "154") (name "unconnected-(U13B-IO_L43P_GCLK5_M1DQ4_1-PadU25)") (class "Default")
      (node (ref "U13") (pin "U25") (pinfunction "IO_L43P_GCLK5_M1DQ4_1_U25") (pintype "passive+no_connect"))
    )
    (net (code "155") (name "unconnected-(U13B-IO_L44N_A2_M1DQ7_1-PadW26)") (class "Default")
      (node (ref "U13") (pin "W26") (pinfunction "IO_L44N_A2_M1DQ7_1_W26") (pintype "passive+no_connect"))
    )
    (net (code "156") (name "unconnected-(U13B-IO_L44P_A3_M1DQ6_1-PadW25)") (class "Default")
      (node (ref "U13") (pin "W25") (pinfunction "IO_L44P_A3_M1DQ6_1_W25") (pintype "passive+no_connect"))
    )
    (net (code "157") (name "unconnected-(U13B-IO_L45N_A0_M1LDQSN_1-PadV26)") (class "Default")
      (node (ref "U13") (pin "V26") (pinfunction "IO_L45N_A0_M1LDQSN_1_V26") (pintype "passive+no_connect"))
    )
    (net (code "158") (name "unconnected-(U13B-IO_L45P_A1_M1LDQS_1-PadV24)") (class "Default")
      (node (ref "U13") (pin "V24") (pinfunction "IO_L45P_A1_M1LDQS_1_V24") (pintype "passive+no_connect"))
    )
    (net (code "159") (name "unconnected-(U13B-IO_L46N_FOE_B_M1DQ3_1-PadT26)") (class "Default")
      (node (ref "U13") (pin "T26") (pinfunction "IO_L46N_FOE_B_M1DQ3_1_T26") (pintype "passive+no_connect"))
    )
    (net (code "160") (name "unconnected-(U13B-IO_L46P_FCS_B_M1DQ2_1-PadT24)") (class "Default")
      (node (ref "U13") (pin "T24") (pinfunction "IO_L46P_FCS_B_M1DQ2_1_T24") (pintype "passive+no_connect"))
    )
    (net (code "161") (name "unconnected-(U13B-IO_L47N_LDC_M1DQ1_1-PadY26)") (class "Default")
      (node (ref "U13") (pin "Y26") (pinfunction "IO_L47N_LDC_M1DQ1_1_Y26") (pintype "passive+no_connect"))
    )
    (net (code "162") (name "unconnected-(U13B-IO_L47P_FWE_B_M1DQ0_1-PadY24)") (class "Default")
      (node (ref "U13") (pin "Y24") (pinfunction "IO_L47P_FWE_B_M1DQ0_1_Y24") (pintype "passive+no_connect"))
    )
    (net (code "163") (name "unconnected-(U13B-IO_L48N_M1DQ9_1-PadAD26)") (class "Default")
      (node (ref "U13") (pin "AD26") (pinfunction "IO_L48N_M1DQ9_1_AD26") (pintype "passive+no_connect"))
    )
    (net (code "164") (name "unconnected-(U13B-IO_L48P_HDC_M1DQ8_1-PadAD24)") (class "Default")
      (node (ref "U13") (pin "AD24") (pinfunction "IO_L48P_HDC_M1DQ8_1_AD24") (pintype "passive+no_connect"))
    )
    (net (code "165") (name "unconnected-(U13B-IO_L49N_M1DQ11_1-PadAB26)") (class "Default")
      (node (ref "U13") (pin "AB26") (pinfunction "IO_L49N_M1DQ11_1_AB26") (pintype "passive+no_connect"))
    )
    (net (code "166") (name "unconnected-(U13B-IO_L49P_M1DQ10_1-PadAB24)") (class "Default")
      (node (ref "U13") (pin "AB24") (pinfunction "IO_L49P_M1DQ10_1_AB24") (pintype "passive+no_connect"))
    )
    (net (code "167") (name "unconnected-(U13B-IO_L50N_M1UDQSN_1-PadAC26)") (class "Default")
      (node (ref "U13") (pin "AC26") (pinfunction "IO_L50N_M1UDQSN_1_AC26") (pintype "passive+no_connect"))
    )
    (net (code "168") (name "unconnected-(U13B-IO_L50P_M1UDQS_1-PadAC25)") (class "Default")
      (node (ref "U13") (pin "AC25") (pinfunction "IO_L50P_M1UDQS_1_AC25") (pintype "passive+no_connect"))
    )
    (net (code "169") (name "unconnected-(U13B-IO_L51N_M1DQ13_1-PadAA26)") (class "Default")
      (node (ref "U13") (pin "AA26") (pinfunction "IO_L51N_M1DQ13_1_AA26") (pintype "passive+no_connect"))
    )
    (net (code "170") (name "unconnected-(U13B-IO_L51P_M1DQ12_1-PadAA25)") (class "Default")
      (node (ref "U13") (pin "AA25") (pinfunction "IO_L51P_M1DQ12_1_AA25") (pintype "passive+no_connect"))
    )
    (net (code "171") (name "unconnected-(U13B-IO_L52N_M1DQ15_1-PadAE26)") (class "Default")
      (node (ref "U13") (pin "AE26") (pinfunction "IO_L52N_M1DQ15_1_AE26") (pintype "passive+no_connect"))
    )
    (net (code "172") (name "unconnected-(U13B-IO_L52P_M1DQ14_1-PadAE25)") (class "Default")
      (node (ref "U13") (pin "AE25") (pinfunction "IO_L52P_M1DQ14_1_AE25") (pintype "passive+no_connect"))
    )
    (net (code "173") (name "unconnected-(U13B-IO_L53N_VREF_1-PadU24)") (class "Default")
      (node (ref "U13") (pin "U24") (pinfunction "IO_L53N_VREF_1_U24") (pintype "passive+no_connect"))
    )
    (net (code "174") (name "unconnected-(U13B-IO_L53P_1-PadT23)") (class "Default")
      (node (ref "U13") (pin "T23") (pinfunction "IO_L53P_1_T23") (pintype "passive+no_connect"))
    )
    (net (code "175") (name "unconnected-(U13B-IO_L69N_VREF_1-PadAB22)") (class "Default")
      (node (ref "U13") (pin "AB22") (pinfunction "IO_L69N_VREF_1_AB22") (pintype "passive+no_connect"))
    )
    (net (code "176") (name "unconnected-(U13B-IO_L69P_1-PadAB21)") (class "Default")
      (node (ref "U13") (pin "AB21") (pinfunction "IO_L69P_1_AB21") (pintype "passive+no_connect"))
    )
    (net (code "177") (name "unconnected-(U13B-IO_L70N_1-PadV20)") (class "Default")
      (node (ref "U13") (pin "V20") (pinfunction "IO_L70N_1_V20") (pintype "passive+no_connect"))
    )
    (net (code "178") (name "unconnected-(U13B-IO_L70P_1-PadU19)") (class "Default")
      (node (ref "U13") (pin "U19") (pinfunction "IO_L70P_1_U19") (pintype "passive+no_connect"))
    )
    (net (code "179") (name "unconnected-(U13B-IO_L71N_1-PadW22)") (class "Default")
      (node (ref "U13") (pin "W22") (pinfunction "IO_L71N_1_W22") (pintype "passive+no_connect"))
    )
    (net (code "180") (name "unconnected-(U13B-IO_L71P_1-PadV22)") (class "Default")
      (node (ref "U13") (pin "V22") (pinfunction "IO_L71P_1_V22") (pintype "passive+no_connect"))
    )
    (net (code "181") (name "unconnected-(U13B-IO_L72N_1-PadY21)") (class "Default")
      (node (ref "U13") (pin "Y21") (pinfunction "IO_L72N_1_Y21") (pintype "passive+no_connect"))
    )
    (net (code "182") (name "unconnected-(U13B-IO_L72P_1-PadY20)") (class "Default")
      (node (ref "U13") (pin "Y20") (pinfunction "IO_L72P_1_Y20") (pintype "passive+no_connect"))
    )
    (net (code "183") (name "unconnected-(U13B-IO_L73N_1-PadAA22)") (class "Default")
      (node (ref "U13") (pin "AA22") (pinfunction "IO_L73N_1_AA22") (pintype "passive+no_connect"))
    )
    (net (code "184") (name "unconnected-(U13B-IO_L73P_1-PadY22)") (class "Default")
      (node (ref "U13") (pin "Y22") (pinfunction "IO_L73P_1_Y22") (pintype "passive+no_connect"))
    )
    (net (code "185") (name "unconnected-(U13B-IO_L74N_DOUT_BUSY_1-PadAF24)") (class "Default")
      (node (ref "U13") (pin "AF24") (pinfunction "IO_L74N_DOUT_BUSY_1_AF24") (pintype "passive+no_connect"))
    )
    (net (code "186") (name "unconnected-(U13B-IO_L74P_AWAKE_1-PadAE23)") (class "Default")
      (node (ref "U13") (pin "AE23") (pinfunction "IO_L74P_AWAKE_1_AE23") (pintype "passive+no_connect"))
    )
  )
)
